# photoduino_shield_v_2_0.net
KiCad netlist of a schematic drawn in EAGLE
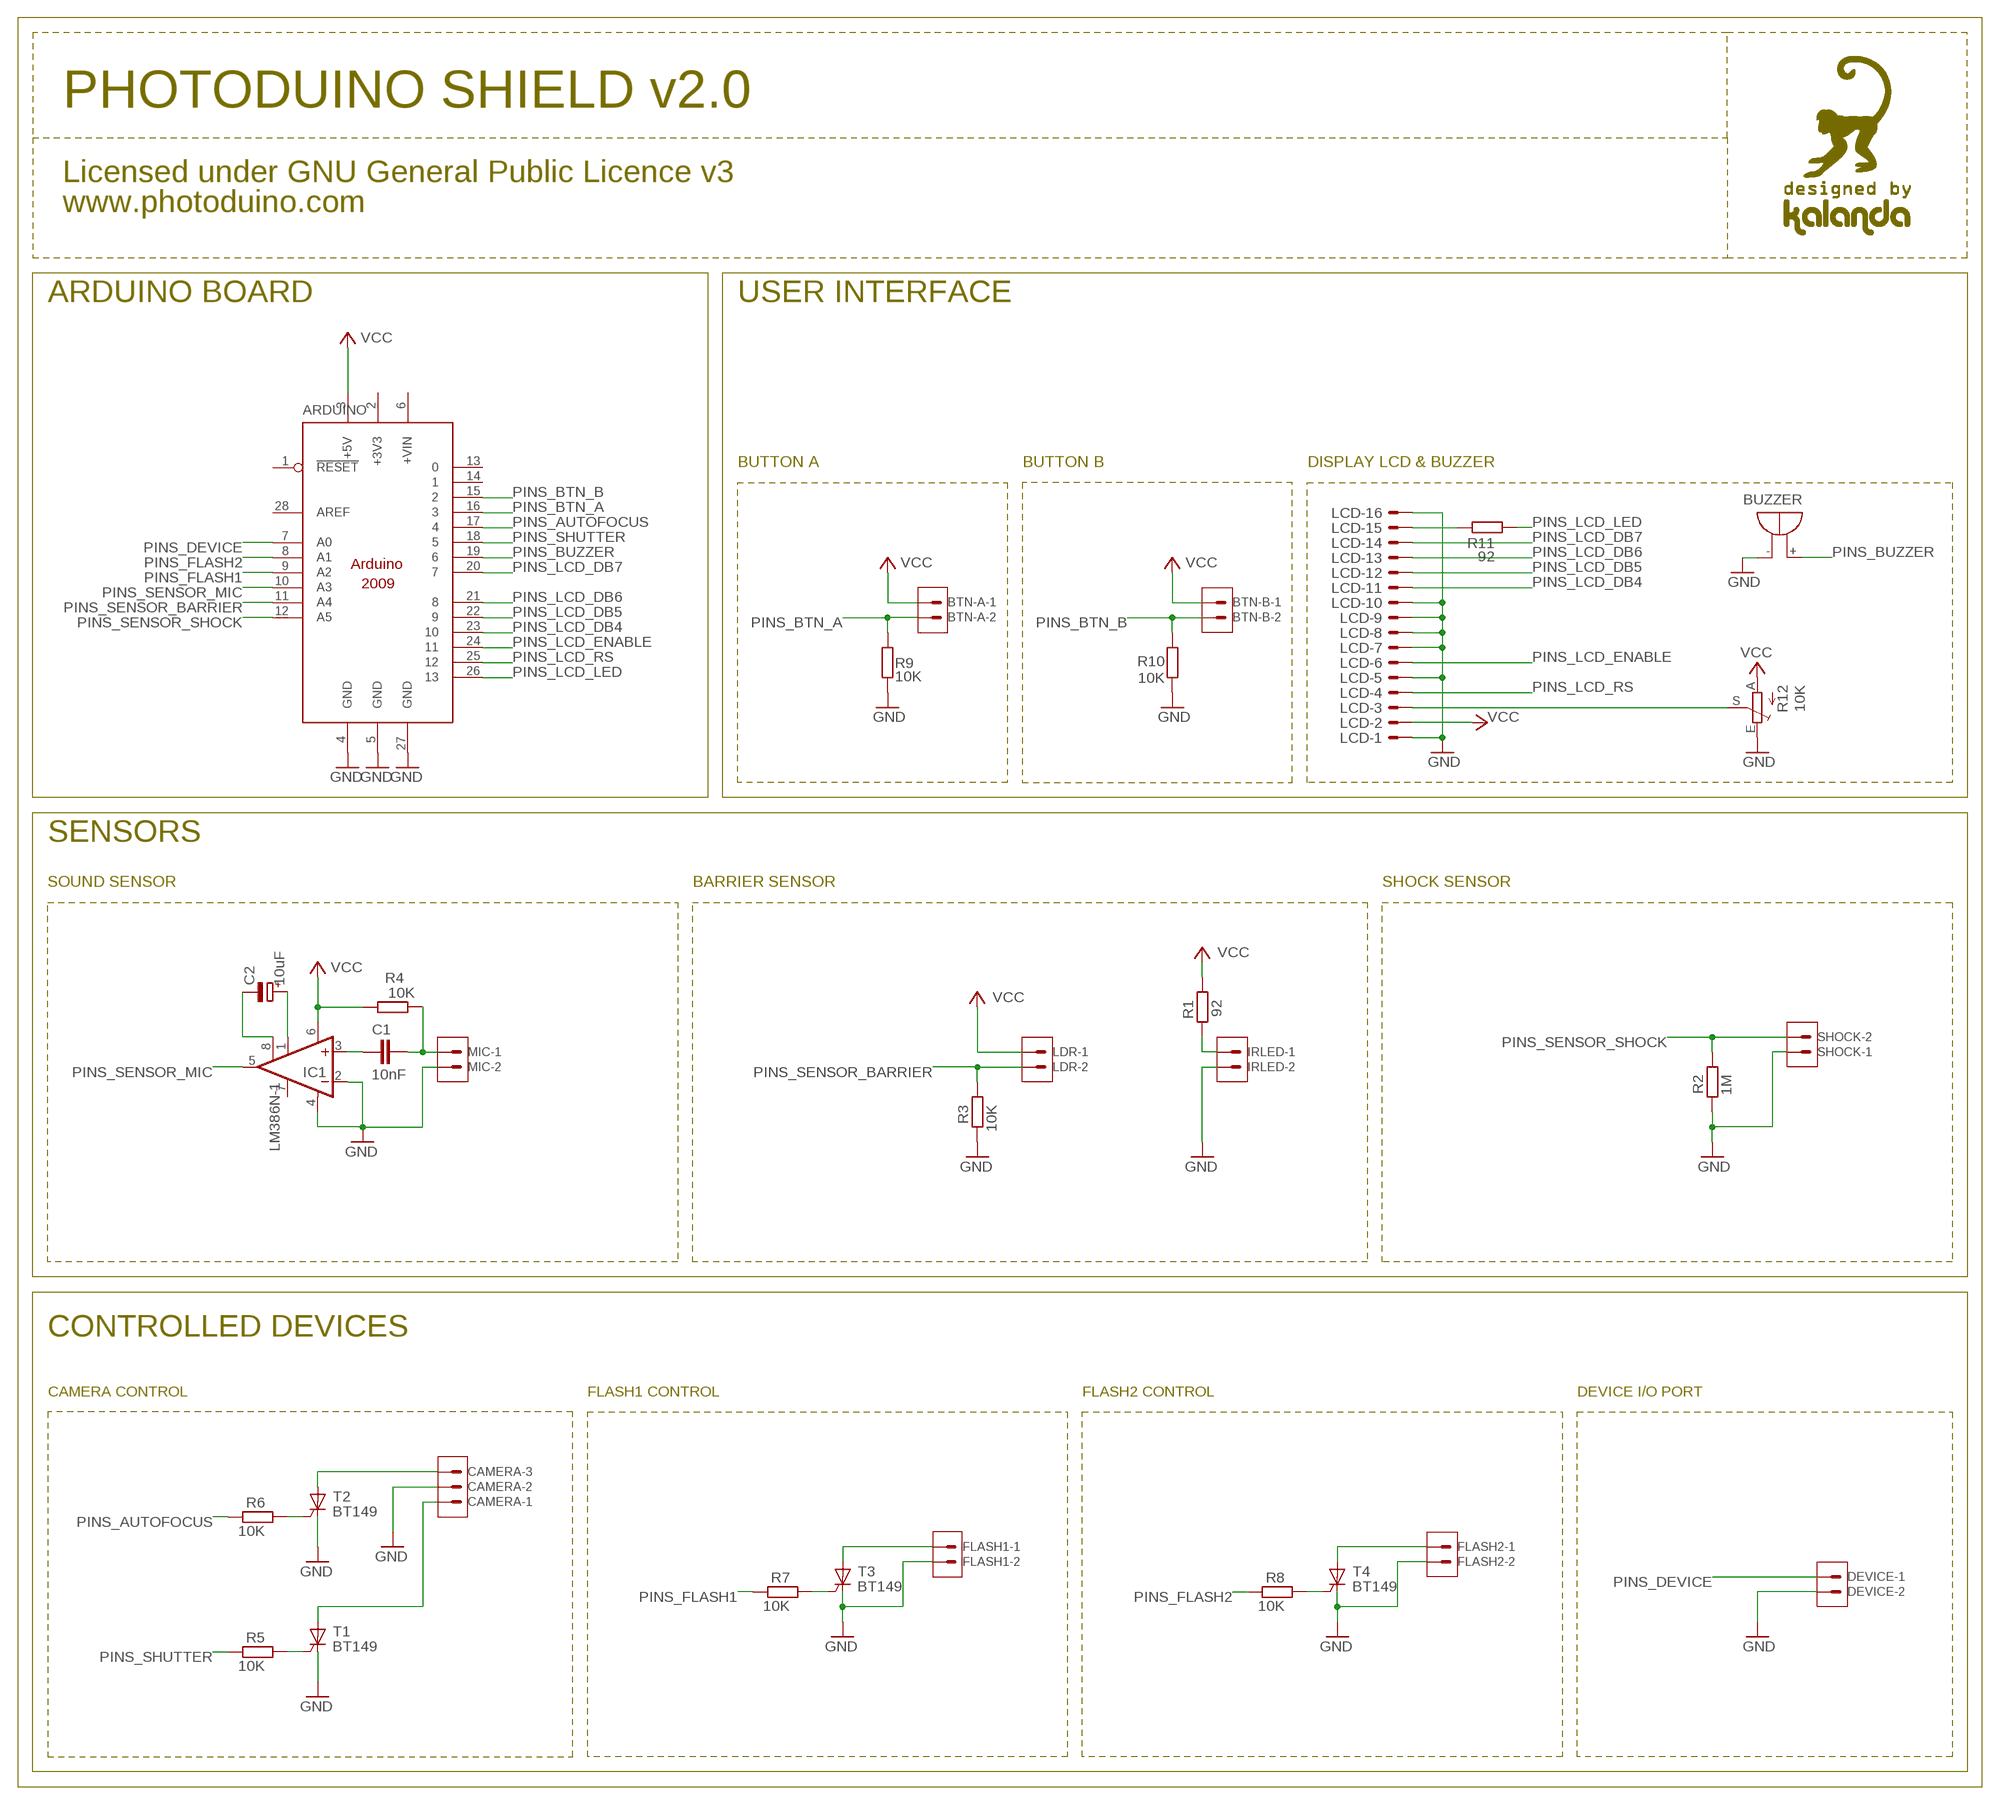
[diagram p0: schematic, sheet 1]

(export (version "E")
  (design (tool "Eeschema 10.0.6"))
  (components
    (comp (ref "ARDUINO")
      (value "ARDUINO2009_11")
      (footprint "eagle-import:ARDUINO2009_1")
      (libsource (lib "eagle-import") (part "ARDUINO2009_11"))
    )
    (comp (ref "BTN-A")
      (value "22-27-2021-02")
      (footprint "eagle-import:6410-02")
      (libsource (lib "eagle-import") (part "22-?-0227-2021"))
    )
    (comp (ref "BTN-B")
      (value "22-27-2021-02")
      (footprint "eagle-import:6410-02")
      (libsource (lib "eagle-import") (part "22-?-0227-2021"))
    )
    (comp (ref "BUZZER")
      (value "F/TMB")
      (footprint "eagle-import:F_TMB")
      (libsource (lib "eagle-import") (part "F/TMB"))
    )
    (comp (ref "C1")
      (value "10nF")
      (footprint "eagle-import:C050-025X075")
      (libsource (lib "eagle-import") (part "C-EU050-025X075"))
    )
    (comp (ref "C2")
      (value "10uF")
      (footprint "eagle-import:E2,5-6")
      (libsource (lib "eagle-import") (part "CPOL-EUE2.5-6"))
    )
    (comp (ref "CAMERA")
      (value "22-27-2031-03")
      (footprint "eagle-import:6410-03")
      (libsource (lib "eagle-import") (part "22-?-0327-2031"))
    )
    (comp (ref "DEVICE")
      (value "22-27-2021-02")
      (footprint "eagle-import:6410-02")
      (libsource (lib "eagle-import") (part "22-?-0227-2021"))
    )
    (comp (ref "FLASH1")
      (value "22-27-2021-02")
      (footprint "eagle-import:6410-02")
      (libsource (lib "eagle-import") (part "22-?-0227-2021"))
    )
    (comp (ref "FLASH2")
      (value "22-27-2021-02")
      (footprint "eagle-import:6410-02")
      (libsource (lib "eagle-import") (part "22-?-0227-2021"))
    )
    (comp (ref "IC1")
      (value "LM386N-1")
      (footprint "eagle-import:DIL08")
      (libsource (lib "eagle-import") (part "LM386?-N1"))
    )
    (comp (ref "IRLED")
      (value "22-27-2021-02")
      (footprint "eagle-import:6410-02")
      (libsource (lib "eagle-import") (part "22-?-0227-2021"))
    )
    (comp (ref "LCD")
      (value "ML16E")
      (footprint "eagle-import:ML16")
      (libsource (lib "eagle-import") (part "ML16E"))
    )
    (comp (ref "LDR")
      (value "22-27-2021-02")
      (footprint "eagle-import:6410-02")
      (libsource (lib "eagle-import") (part "22-?-0227-2021"))
    )
    (comp (ref "LOGO")
      (value "LOGOKALANDA")
      (footprint "eagle-import:LOGOKALANDA")
      (libsource (lib "eagle-import") (part "LOGOKALANDA"))
    )
    (comp (ref "MIC")
      (value "22-27-2021-02")
      (footprint "eagle-import:6410-02")
      (libsource (lib "eagle-import") (part "22-?-0227-2021"))
    )
    (comp (ref "R1")
      (value "92")
      (footprint "eagle-import:0207_7")
      (libsource (lib "eagle-import") (part "R-EU_0207/7"))
    )
    (comp (ref "R2")
      (value "1M")
      (footprint "eagle-import:0207_7")
      (libsource (lib "eagle-import") (part "R-EU_0207/7"))
    )
    (comp (ref "R3")
      (value "10K")
      (footprint "eagle-import:0207_7")
      (libsource (lib "eagle-import") (part "R-EU_0207/7"))
    )
    (comp (ref "R4")
      (value "10K")
      (footprint "eagle-import:0207_7")
      (libsource (lib "eagle-import") (part "R-EU_0207/7"))
    )
    (comp (ref "R5")
      (value "10K")
      (footprint "eagle-import:0207_7")
      (libsource (lib "eagle-import") (part "R-EU_0207/7"))
    )
    (comp (ref "R6")
      (value "10K")
      (footprint "eagle-import:0207_7")
      (libsource (lib "eagle-import") (part "R-EU_0207/7"))
    )
    (comp (ref "R7")
      (value "10K")
      (footprint "eagle-import:0207_7")
      (libsource (lib "eagle-import") (part "R-EU_0207/7"))
    )
    (comp (ref "R8")
      (value "10K")
      (footprint "eagle-import:0207_7")
      (libsource (lib "eagle-import") (part "R-EU_0207/7"))
    )
    (comp (ref "R9")
      (value "10K")
      (footprint "eagle-import:0207_7")
      (libsource (lib "eagle-import") (part "R-EU_0207/7"))
    )
    (comp (ref "R10")
      (value "10K")
      (footprint "eagle-import:0207_7")
      (libsource (lib "eagle-import") (part "R-EU_0207/7"))
    )
    (comp (ref "R11")
      (value "92")
      (footprint "eagle-import:0207_7")
      (libsource (lib "eagle-import") (part "R-EU_0207/7"))
    )
    (comp (ref "R12")
      (value "10K")
      (footprint "eagle-import:RJ9W")
      (libsource (lib "eagle-import") (part "TRIM_EU-RJ9W"))
    )
    (comp (ref "SHOCK")
      (value "22-27-2021-02")
      (footprint "eagle-import:6410-02")
      (libsource (lib "eagle-import") (part "22-?-0227-2021"))
    )
    (comp (ref "T1")
      (value "BT149")
      (footprint "eagle-import:TO92-4")
      (libsource (lib "eagle-import") (part "BT149"))
    )
    (comp (ref "T2")
      (value "BT149")
      (footprint "eagle-import:TO92-4")
      (libsource (lib "eagle-import") (part "BT149"))
    )
    (comp (ref "T3")
      (value "BT149")
      (footprint "eagle-import:TO92-4")
      (libsource (lib "eagle-import") (part "BT149"))
    )
    (comp (ref "T4")
      (value "BT149")
      (footprint "eagle-import:TO92-4")
      (libsource (lib "eagle-import") (part "BT149"))
    )
  )
  (nets
    (net (code "1") (name "/+3V3") (class "Default")
      (node (ref "ARDUINO") (pin "2") (pinfunction "+3V3_2") (pintype "power_in"))
    )
    (net (code "2") (name "/PINS_AUTOFOCUS") (class "Default")
      (node (ref "ARDUINO") (pin "17") (pinfunction "4_17") (pintype "bidirectional"))
      (node (ref "R6") (pin "2") (pinfunction "2_2") (pintype "passive"))
    )
    (net (code "3") (name "/PINS_BTN_A") (class "Default")
      (node (ref "ARDUINO") (pin "16") (pinfunction "3_16") (pintype "bidirectional"))
      (node (ref "BTN-A") (pin "2") (pinfunction "S_2") (pintype "passive"))
      (node (ref "R9") (pin "2") (pinfunction "2_2") (pintype "passive"))
    )
    (net (code "4") (name "/PINS_BTN_B") (class "Default")
      (node (ref "ARDUINO") (pin "15") (pinfunction "2_15") (pintype "bidirectional"))
      (node (ref "BTN-B") (pin "2") (pinfunction "S_2") (pintype "passive"))
      (node (ref "R10") (pin "1") (pinfunction "1_1") (pintype "passive"))
    )
    (net (code "5") (name "/PINS_BUZZER") (class "Default")
      (node (ref "ARDUINO") (pin "19") (pinfunction "6_19") (pintype "bidirectional"))
      (node (ref "BUZZER") (pin "+") (pinfunction "+_+") (pintype "passive"))
    )
    (net (code "6") (name "/PINS_DEVICE") (class "Default")
      (node (ref "ARDUINO") (pin "7") (pinfunction "A0_7") (pintype "bidirectional"))
      (node (ref "DEVICE") (pin "1") (pinfunction "S_1") (pintype "passive"))
    )
    (net (code "7") (name "/PINS_FLASH1") (class "Default")
      (node (ref "ARDUINO") (pin "9") (pinfunction "A2_9") (pintype "bidirectional"))
      (node (ref "R7") (pin "2") (pinfunction "2_2") (pintype "passive"))
    )
    (net (code "8") (name "/PINS_FLASH2") (class "Default")
      (node (ref "ARDUINO") (pin "8") (pinfunction "A1_8") (pintype "bidirectional"))
      (node (ref "R8") (pin "2") (pinfunction "2_2") (pintype "passive"))
    )
    (net (code "9") (name "/PINS_LCD_DB4") (class "Default")
      (node (ref "ARDUINO") (pin "23") (pinfunction "10_23") (pintype "bidirectional"))
      (node (ref "LCD") (pin "11") (pinfunction "S_11") (pintype "passive"))
    )
    (net (code "10") (name "/PINS_LCD_DB5") (class "Default")
      (node (ref "ARDUINO") (pin "22") (pinfunction "9_22") (pintype "bidirectional"))
      (node (ref "LCD") (pin "12") (pinfunction "S_12") (pintype "passive"))
    )
    (net (code "11") (name "/PINS_LCD_DB6") (class "Default")
      (node (ref "ARDUINO") (pin "21") (pinfunction "8_21") (pintype "bidirectional"))
      (node (ref "LCD") (pin "13") (pinfunction "S_13") (pintype "passive"))
    )
    (net (code "12") (name "/PINS_LCD_DB7") (class "Default")
      (node (ref "ARDUINO") (pin "20") (pinfunction "7_20") (pintype "bidirectional"))
      (node (ref "LCD") (pin "14") (pinfunction "S_14") (pintype "passive"))
    )
    (net (code "13") (name "/PINS_LCD_ENABLE") (class "Default")
      (node (ref "ARDUINO") (pin "24") (pinfunction "11_24") (pintype "bidirectional"))
      (node (ref "LCD") (pin "6") (pinfunction "S_6") (pintype "passive"))
    )
    (net (code "14") (name "/PINS_LCD_LED") (class "Default")
      (node (ref "ARDUINO") (pin "26") (pinfunction "13_26") (pintype "bidirectional"))
      (node (ref "R11") (pin "1") (pinfunction "1_1") (pintype "passive"))
    )
    (net (code "15") (name "/PINS_LCD_RS") (class "Default")
      (node (ref "ARDUINO") (pin "25") (pinfunction "12_25") (pintype "bidirectional"))
      (node (ref "LCD") (pin "4") (pinfunction "S_4") (pintype "passive"))
    )
    (net (code "16") (name "/PINS_SENSOR_BARRIER") (class "Default")
      (node (ref "ARDUINO") (pin "11") (pinfunction "A4_11") (pintype "bidirectional"))
      (node (ref "LDR") (pin "2") (pinfunction "S_2") (pintype "passive"))
      (node (ref "R3") (pin "1") (pinfunction "1_1") (pintype "passive"))
    )
    (net (code "17") (name "/PINS_SENSOR_MIC") (class "Default")
      (node (ref "ARDUINO") (pin "10") (pinfunction "A3_10") (pintype "bidirectional"))
      (node (ref "IC1") (pin "5") (pinfunction "OUT_5") (pintype "output"))
    )
    (net (code "18") (name "/PINS_SENSOR_SHOCK") (class "Default")
      (node (ref "ARDUINO") (pin "12") (pinfunction "A5_12") (pintype "bidirectional"))
      (node (ref "R2") (pin "1") (pinfunction "1_1") (pintype "passive"))
      (node (ref "SHOCK") (pin "2") (pinfunction "S_2") (pintype "passive"))
    )
    (net (code "19") (name "/PINS_SHUTTER") (class "Default")
      (node (ref "ARDUINO") (pin "18") (pinfunction "5_18") (pintype "bidirectional"))
      (node (ref "R5") (pin "2") (pinfunction "2_2") (pintype "passive"))
    )
    (net (code "20") (name "GND") (class "Default")
      (node (ref "ARDUINO") (pin "27") (pinfunction "GND_27") (pintype "power_in"))
      (node (ref "ARDUINO") (pin "4") (pinfunction "GND_4") (pintype "power_in"))
      (node (ref "ARDUINO") (pin "5") (pinfunction "GND_5") (pintype "power_in"))
      (node (ref "BUZZER") (pin "-") (pinfunction "-_-") (pintype "passive"))
      (node (ref "CAMERA") (pin "2") (pinfunction "S_2") (pintype "passive"))
      (node (ref "DEVICE") (pin "2") (pinfunction "S_2") (pintype "passive"))
      (node (ref "FLASH1") (pin "2") (pinfunction "S_2") (pintype "passive"))
      (node (ref "FLASH2") (pin "2") (pinfunction "S_2") (pintype "passive"))
      (node (ref "IC1") (pin "2") (pinfunction "-IN_2") (pintype "input"))
      (node (ref "IC1") (pin "4") (pinfunction "GND_4") (pintype "power_in"))
      (node (ref "IRLED") (pin "2") (pinfunction "S_2") (pintype "passive"))
      (node (ref "LCD") (pin "1") (pinfunction "S_1") (pintype "passive"))
      (node (ref "LCD") (pin "10") (pinfunction "S_10") (pintype "passive"))
      (node (ref "LCD") (pin "16") (pinfunction "S_16") (pintype "passive"))
      (node (ref "LCD") (pin "5") (pinfunction "S_5") (pintype "passive"))
      (node (ref "LCD") (pin "7") (pinfunction "S_7") (pintype "passive"))
      (node (ref "LCD") (pin "8") (pinfunction "S_8") (pintype "passive"))
      (node (ref "LCD") (pin "9") (pinfunction "S_9") (pintype "passive"))
      (node (ref "MIC") (pin "2") (pinfunction "S_2") (pintype "passive"))
      (node (ref "R10") (pin "2") (pinfunction "2_2") (pintype "passive"))
      (node (ref "R12") (pin "E") (pinfunction "E_E") (pintype "passive"))
      (node (ref "R2") (pin "2") (pinfunction "2_2") (pintype "passive"))
      (node (ref "R3") (pin "2") (pinfunction "2_2") (pintype "passive"))
      (node (ref "R9") (pin "1") (pinfunction "1_1") (pintype "passive"))
      (node (ref "SHOCK") (pin "1") (pinfunction "S_1") (pintype "passive"))
      (node (ref "T1") (pin "C") (pinfunction "C_C") (pintype "passive"))
      (node (ref "T2") (pin "C") (pinfunction "C_C") (pintype "passive"))
      (node (ref "T3") (pin "C") (pinfunction "C_C") (pintype "passive"))
      (node (ref "T4") (pin "C") (pinfunction "C_C") (pintype "passive"))
    )
    (net (code "21") (name "Net-(C2-Pad+)") (class "Default")
      (node (ref "C2") (pin "+") (pinfunction "+_+") (pintype "passive"))
      (node (ref "IC1") (pin "1") (pinfunction "GAIN_1") (pintype "passive"))
    )
    (net (code "22") (name "Net-(C2-Pad-)") (class "Default")
      (node (ref "C2") (pin "-") (pinfunction "-_-") (pintype "passive"))
      (node (ref "IC1") (pin "8") (pinfunction "GAIN_8") (pintype "passive"))
    )
    (net (code "23") (name "Net-(CAMERAA-S)") (class "Default")
      (node (ref "CAMERA") (pin "1") (pinfunction "S_1") (pintype "passive"))
      (node (ref "T1") (pin "A") (pinfunction "A_A") (pintype "passive"))
    )
    (net (code "24") (name "Net-(CAMERAC-S)") (class "Default")
      (node (ref "CAMERA") (pin "3") (pinfunction "S_3") (pintype "passive"))
      (node (ref "T2") (pin "A") (pinfunction "A_A") (pintype "passive"))
    )
    (net (code "25") (name "Net-(FLASH1A-S)") (class "Default")
      (node (ref "FLASH1") (pin "1") (pinfunction "S_1") (pintype "passive"))
      (node (ref "T3") (pin "A") (pinfunction "A_A") (pintype "passive"))
    )
    (net (code "26") (name "Net-(FLASH2A-S)") (class "Default")
      (node (ref "FLASH2") (pin "1") (pinfunction "S_1") (pintype "passive"))
      (node (ref "T4") (pin "A") (pinfunction "A_A") (pintype "passive"))
    )
    (net (code "27") (name "Net-(IC1-+IN)") (class "Default")
      (node (ref "C1") (pin "1") (pinfunction "1_1") (pintype "passive"))
      (node (ref "IC1") (pin "3") (pinfunction "+IN_3") (pintype "input"))
    )
    (net (code "28") (name "Net-(IRLEDA-S)") (class "Default")
      (node (ref "IRLED") (pin "1") (pinfunction "S_1") (pintype "passive"))
      (node (ref "R1") (pin "2") (pinfunction "2_2") (pintype "passive"))
    )
    (net (code "29") (name "Net-(LCDG-S)") (class "Default")
      (node (ref "LCD") (pin "15") (pinfunction "S_15") (pintype "passive"))
      (node (ref "R11") (pin "2") (pinfunction "2_2") (pintype "passive"))
    )
    (net (code "30") (name "Net-(LCDJ-S)") (class "Default")
      (node (ref "LCD") (pin "3") (pinfunction "S_3") (pintype "passive"))
      (node (ref "R12") (pin "S") (pinfunction "S_S") (pintype "passive"))
    )
    (net (code "31") (name "Net-(MICA-S)") (class "Default")
      (node (ref "C1") (pin "2") (pinfunction "2_2") (pintype "passive"))
      (node (ref "MIC") (pin "1") (pinfunction "S_1") (pintype "passive"))
      (node (ref "R4") (pin "1") (pinfunction "1_1") (pintype "passive"))
    )
    (net (code "32") (name "Net-(R5-Pad1)") (class "Default")
      (node (ref "R5") (pin "1") (pinfunction "1_1") (pintype "passive"))
      (node (ref "T1") (pin "G") (pinfunction "G_G") (pintype "passive"))
    )
    (net (code "33") (name "Net-(R6-Pad1)") (class "Default")
      (node (ref "R6") (pin "1") (pinfunction "1_1") (pintype "passive"))
      (node (ref "T2") (pin "G") (pinfunction "G_G") (pintype "passive"))
    )
    (net (code "34") (name "Net-(R7-Pad1)") (class "Default")
      (node (ref "R7") (pin "1") (pinfunction "1_1") (pintype "passive"))
      (node (ref "T3") (pin "G") (pinfunction "G_G") (pintype "passive"))
    )
    (net (code "35") (name "Net-(R8-Pad1)") (class "Default")
      (node (ref "R8") (pin "1") (pinfunction "1_1") (pintype "passive"))
      (node (ref "T4") (pin "G") (pinfunction "G_G") (pintype "passive"))
    )
    (net (code "36") (name "VCC") (class "Default")
      (node (ref "ARDUINO") (pin "3") (pinfunction "+5V_3") (pintype "power_in"))
      (node (ref "BTN-A") (pin "1") (pinfunction "S_1") (pintype "passive"))
      (node (ref "BTN-B") (pin "1") (pinfunction "S_1") (pintype "passive"))
      (node (ref "IC1") (pin "6") (pinfunction "VS_6") (pintype "power_in"))
      (node (ref "LCD") (pin "2") (pinfunction "S_2") (pintype "passive"))
      (node (ref "LDR") (pin "1") (pinfunction "S_1") (pintype "passive"))
      (node (ref "R1") (pin "1") (pinfunction "1_1") (pintype "passive"))
      (node (ref "R12") (pin "A") (pinfunction "A_A") (pintype "passive"))
      (node (ref "R4") (pin "2") (pinfunction "2_2") (pintype "passive"))
    )
    (net (code "37") (name "unconnected-(ARDUINO-+VIN-Pad6)") (class "Default")
      (node (ref "ARDUINO") (pin "6") (pinfunction "+VIN_6") (pintype "bidirectional"))
    )
    (net (code "38") (name "unconnected-(ARDUINO-0-Pad13)") (class "Default")
      (node (ref "ARDUINO") (pin "13") (pinfunction "0_13") (pintype "bidirectional"))
    )
    (net (code "39") (name "unconnected-(ARDUINO-1-Pad14)") (class "Default")
      (node (ref "ARDUINO") (pin "14") (pinfunction "1_14") (pintype "bidirectional"))
    )
    (net (code "40") (name "unconnected-(ARDUINO-AREF-Pad28)") (class "Default")
      (node (ref "ARDUINO") (pin "28") (pinfunction "AREF_28") (pintype "bidirectional"))
    )
    (net (code "41") (name "unconnected-(ARDUINO-~{RESET}-Pad1)") (class "Default")
      (node (ref "ARDUINO") (pin "1") (pinfunction "~{RESET}_1") (pintype "bidirectional"))
    )
    (net (code "42") (name "unconnected-(IC1-BYPASS-Pad7)") (class "Default")
      (node (ref "IC1") (pin "7") (pinfunction "BYPASS_7") (pintype "passive"))
    )
  )
)
